# Esquematico.net
KiCad netlist of a schematic drawn in Altium Designer
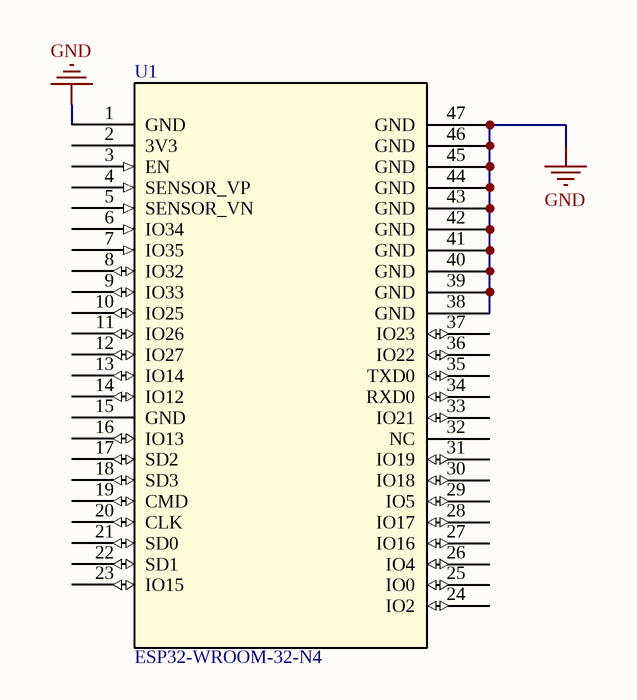
[diagram p0: Esquematico.SchDoc]

(export (version "E")
  (design (tool "Eeschema 10.0.6"))
  (components
    (comp (ref "U1")
      (value "ESP32-WROOM-32-N4")
      (footprint "MOD_ESP32-WROOM-32_EXP")
      (description "No Description Available")
      (libsource (lib "Schlib1") (part "ESP32-WROOM-32-N4"))
    )
  )
  (nets
    (net (code "1") (name "GND") (class "Default")
      (node (ref "U1") (pin "1") (pinfunction "GND_1") (pintype "power_in"))
      (node (ref "U1") (pin "38") (pinfunction "GND_38") (pintype "power_in"))
      (node (ref "U1") (pin "39") (pinfunction "GND_39") (pintype "power_in"))
      (node (ref "U1") (pin "40") (pinfunction "GND_40") (pintype "power_in"))
      (node (ref "U1") (pin "41") (pinfunction "GND_41") (pintype "power_in"))
      (node (ref "U1") (pin "42") (pinfunction "GND_42") (pintype "power_in"))
      (node (ref "U1") (pin "43") (pinfunction "GND_43") (pintype "power_in"))
      (node (ref "U1") (pin "44") (pinfunction "GND_44") (pintype "power_in"))
      (node (ref "U1") (pin "45") (pinfunction "GND_45") (pintype "power_in"))
      (node (ref "U1") (pin "46") (pinfunction "GND_46") (pintype "power_in"))
      (node (ref "U1") (pin "47") (pinfunction "GND_47") (pintype "power_in"))
    )
    (net (code "2") (name "unconnected-(U1-3V3-Pad2)") (class "Default")
      (node (ref "U1") (pin "2") (pinfunction "3V3_2") (pintype "power_in"))
    )
    (net (code "3") (name "unconnected-(U1-CLK-Pad20)") (class "Default")
      (node (ref "U1") (pin "20") (pinfunction "CLK_20") (pintype "bidirectional"))
    )
    (net (code "4") (name "unconnected-(U1-CMD-Pad19)") (class "Default")
      (node (ref "U1") (pin "19") (pinfunction "CMD_19") (pintype "bidirectional"))
    )
    (net (code "5") (name "unconnected-(U1-EN-Pad3)") (class "Default")
      (node (ref "U1") (pin "3") (pinfunction "EN_3") (pintype "input"))
    )
    (net (code "6") (name "unconnected-(U1-GND-Pad15)") (class "Default")
      (node (ref "U1") (pin "15") (pinfunction "GND_15") (pintype "power_in"))
    )
    (net (code "7") (name "unconnected-(U1-IO0-Pad25)") (class "Default")
      (node (ref "U1") (pin "25") (pinfunction "IO0_25") (pintype "bidirectional"))
    )
    (net (code "8") (name "unconnected-(U1-IO2-Pad24)") (class "Default")
      (node (ref "U1") (pin "24") (pinfunction "IO2_24") (pintype "bidirectional"))
    )
    (net (code "9") (name "unconnected-(U1-IO4-Pad26)") (class "Default")
      (node (ref "U1") (pin "26") (pinfunction "IO4_26") (pintype "bidirectional"))
    )
    (net (code "10") (name "unconnected-(U1-IO5-Pad29)") (class "Default")
      (node (ref "U1") (pin "29") (pinfunction "IO5_29") (pintype "bidirectional"))
    )
    (net (code "11") (name "unconnected-(U1-IO12-Pad14)") (class "Default")
      (node (ref "U1") (pin "14") (pinfunction "IO12_14") (pintype "bidirectional"))
    )
    (net (code "12") (name "unconnected-(U1-IO13-Pad16)") (class "Default")
      (node (ref "U1") (pin "16") (pinfunction "IO13_16") (pintype "bidirectional"))
    )
    (net (code "13") (name "unconnected-(U1-IO14-Pad13)") (class "Default")
      (node (ref "U1") (pin "13") (pinfunction "IO14_13") (pintype "bidirectional"))
    )
    (net (code "14") (name "unconnected-(U1-IO15-Pad23)") (class "Default")
      (node (ref "U1") (pin "23") (pinfunction "IO15_23") (pintype "bidirectional"))
    )
    (net (code "15") (name "unconnected-(U1-IO16-Pad27)") (class "Default")
      (node (ref "U1") (pin "27") (pinfunction "IO16_27") (pintype "bidirectional"))
    )
    (net (code "16") (name "unconnected-(U1-IO17-Pad28)") (class "Default")
      (node (ref "U1") (pin "28") (pinfunction "IO17_28") (pintype "bidirectional"))
    )
    (net (code "17") (name "unconnected-(U1-IO18-Pad30)") (class "Default")
      (node (ref "U1") (pin "30") (pinfunction "IO18_30") (pintype "bidirectional"))
    )
    (net (code "18") (name "unconnected-(U1-IO19-Pad31)") (class "Default")
      (node (ref "U1") (pin "31") (pinfunction "IO19_31") (pintype "bidirectional"))
    )
    (net (code "19") (name "unconnected-(U1-IO21-Pad33)") (class "Default")
      (node (ref "U1") (pin "33") (pinfunction "IO21_33") (pintype "bidirectional"))
    )
    (net (code "20") (name "unconnected-(U1-IO22-Pad36)") (class "Default")
      (node (ref "U1") (pin "36") (pinfunction "IO22_36") (pintype "bidirectional"))
    )
    (net (code "21") (name "unconnected-(U1-IO23-Pad37)") (class "Default")
      (node (ref "U1") (pin "37") (pinfunction "IO23_37") (pintype "bidirectional"))
    )
    (net (code "22") (name "unconnected-(U1-IO25-Pad10)") (class "Default")
      (node (ref "U1") (pin "10") (pinfunction "IO25_10") (pintype "bidirectional"))
    )
    (net (code "23") (name "unconnected-(U1-IO26-Pad11)") (class "Default")
      (node (ref "U1") (pin "11") (pinfunction "IO26_11") (pintype "bidirectional"))
    )
    (net (code "24") (name "unconnected-(U1-IO27-Pad12)") (class "Default")
      (node (ref "U1") (pin "12") (pinfunction "IO27_12") (pintype "bidirectional"))
    )
    (net (code "25") (name "unconnected-(U1-IO32-Pad8)") (class "Default")
      (node (ref "U1") (pin "8") (pinfunction "IO32_8") (pintype "bidirectional"))
    )
    (net (code "26") (name "unconnected-(U1-IO33-Pad9)") (class "Default")
      (node (ref "U1") (pin "9") (pinfunction "IO33_9") (pintype "bidirectional"))
    )
    (net (code "27") (name "unconnected-(U1-IO34-Pad6)") (class "Default")
      (node (ref "U1") (pin "6") (pinfunction "IO34_6") (pintype "input"))
    )
    (net (code "28") (name "unconnected-(U1-IO35-Pad7)") (class "Default")
      (node (ref "U1") (pin "7") (pinfunction "IO35_7") (pintype "input"))
    )
    (net (code "29") (name "unconnected-(U1-NC-Pad32)") (class "Default")
      (node (ref "U1") (pin "32") (pinfunction "NC_32") (pintype "passive"))
    )
    (net (code "30") (name "unconnected-(U1-RXD0-Pad34)") (class "Default")
      (node (ref "U1") (pin "34") (pinfunction "RXD0_34") (pintype "bidirectional"))
    )
    (net (code "31") (name "unconnected-(U1-SD0-Pad21)") (class "Default")
      (node (ref "U1") (pin "21") (pinfunction "SD0_21") (pintype "bidirectional"))
    )
    (net (code "32") (name "unconnected-(U1-SD1-Pad22)") (class "Default")
      (node (ref "U1") (pin "22") (pinfunction "SD1_22") (pintype "bidirectional"))
    )
    (net (code "33") (name "unconnected-(U1-SD2-Pad17)") (class "Default")
      (node (ref "U1") (pin "17") (pinfunction "SD2_17") (pintype "bidirectional"))
    )
    (net (code "34") (name "unconnected-(U1-SD3-Pad18)") (class "Default")
      (node (ref "U1") (pin "18") (pinfunction "SD3_18") (pintype "bidirectional"))
    )
    (net (code "35") (name "unconnected-(U1-SENSOR_VN-Pad5)") (class "Default")
      (node (ref "U1") (pin "5") (pinfunction "SENSOR_VN_5") (pintype "input"))
    )
    (net (code "36") (name "unconnected-(U1-SENSOR_VP-Pad4)") (class "Default")
      (node (ref "U1") (pin "4") (pinfunction "SENSOR_VP_4") (pintype "input"))
    )
    (net (code "37") (name "unconnected-(U1-TXD0-Pad35)") (class "Default")
      (node (ref "U1") (pin "35") (pinfunction "TXD0_35") (pintype "bidirectional"))
    )
  )
)
